# TIASch.net
KiCad netlist of a schematic drawn in Altium Designer
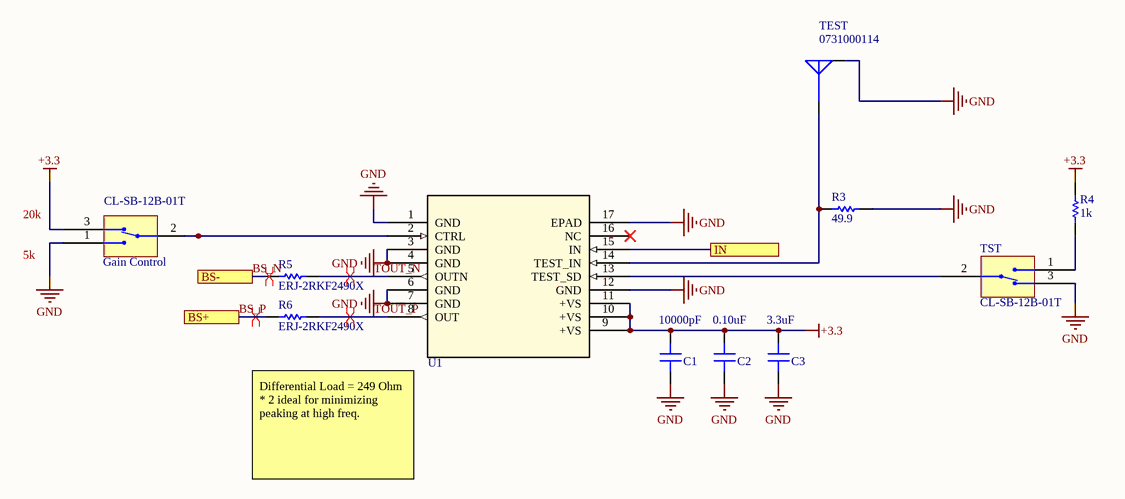
[diagram p0: TIASch.SchDoc]

(export (version "E")
  (design (tool "Eeschema 10.0.6"))
  (components
    (comp (ref "C1")
      (value "10000pF")
      (footprint "CAP 0402/1005")
      (description "CAP CER 10000PF 16V X7R 0402")
      (fields (field (name "PART NUMBER") "C0402C103J4RACTU") (field (name "MANUFACTURER") "Kemet"))
      (libsource (lib "Celestial Library Database") (part "Capacitor"))
    )
    (comp (ref "C2")
      (value "0.10uF")
      (footprint "CAP 0402/1005")
      (description "CAP CER 0.1UF 16V X7R 0402")
      (fields
        (field (name "PART NUMBER") "GRM155R71C104JA88D")
        (field (name "MANUFACTURER") "Murata Electronics North America")
      )
      (libsource (lib "Celestial Library Database") (part "Capacitor"))
    )
    (comp (ref "C3")
      (value "3.3uF")
      (footprint "CAP 0805/2012")
      (description "CAP CER 3.3UF 16V X7R 0805")
      (fields
        (field (name "PART NUMBER") "C2012X7R1C335K125AB")
        (field (name "MANUFACTURER") "TDK Corporation")
      )
      (libsource (lib "Celestial Library Database") (part "Capacitor"))
    )
    (comp (ref "Gain Control")
      (value "CL-SB-12B-01T")
      (footprint "SW_CL-SB-12B-01")
      (description "SWITCH SLIDE SPDT 200MA 12V")
      (fields (field (name "MANUFACTURER") "Nidec Copal Electronics"))
      (libsource (lib "") (part "CL-SB-12B-01T_1"))
    )
    (comp (ref "R3")
      (value "49.9")
      (footprint "RESC1005X40X25NL05T05")
      (fields (field (name "MANUFACTURER") "Panasonic") (field (name "PART NUMBER") "ERJ-2RKF49R9X"))
      (libsource (lib "Altium Content Vault") (part "RES"))
    )
    (comp (ref "R4")
      (value "1k")
      (footprint "RESC1005X40X25NL05T05")
      (description "Chip Resistor, 1 KOhm, +/- 1%, 100 mW, -55 to 155 degC, 0402 (1005 Metric), RoHS, Tape and Reel")
      (fields (field (name "PARTNUMBER") "ERJ-2RKF1001X") (field (name "MANUFACTURER") "Basic Passives"))
      (libsource (lib "Altium Content Vault") (part "RES-2"))
    )
    (comp (ref "R5")
      (value "ERJ-2RKF2490X")
      (footprint "RESC1005X40X25NL05T05")
      (fields (field (name "MANUFACTURER") "Panasonic"))
      (libsource (lib "Altium Content Vault") (part "RES"))
    )
    (comp (ref "R6")
      (value "ERJ-2RKF2490X")
      (footprint "RESC1005X40X25NL05T05")
      (fields (field (name "MANUFACTURER") "Panasonic"))
      (libsource (lib "Altium Content Vault") (part "RES"))
    )
    (comp (ref "TEST")
      (value "0731000114")
      (footprint "MOLEX SD-73100-0114")
      (description "CONN SMA RCPT R/A 50 OHM PCB")
      (fields (field (name "MANUFACTURER") "Molex"))
      (libsource (lib "Celestial Library Database") (part "RF Connector - SMA"))
    )
    (comp (ref "TST")
      (value "CL-SB-12B-01T")
      (footprint "SW_CL-SB-12B-01")
      (description "SWITCH SLIDE SPDT 200MA 12V")
      (fields (field (name "MANUFACTURER") "Nidec Copal Electronics"))
      (libsource (lib "Celestial Library Database") (part "CL-SB-12B-01T"))
    )
    (comp (ref "U1")
      (value "OPA857")
      (footprint "TI VQFN-16 (3x3)")
      (description "IC OPAMP GP 1 CIRCUIT 16VQFN")
      (fields
        (field (name "MANUFACTURER_PART_NUMBER") "OPA857IRGTT")
        (field (name "MANUFACTURER") "Texas Instruments")
        (field (name "COPYRIGHT") "Copyright (C) 2018 Accelerated Designs. All rights reserved")
      )
      (libsource (lib "Celestial Library Database") (part "OPA857IRGTT"))
    )
  )
  (nets
    (net (code "1") (name "+3.3") (class "Default")
      (node (ref "C1") (pin "2") (pinfunction "2_2") (pintype "passive"))
      (node (ref "C2") (pin "2") (pinfunction "2_2") (pintype "passive"))
      (node (ref "C3") (pin "2") (pinfunction "2_2") (pintype "passive"))
      (node (ref "Gain Control") (pin "3") (pinfunction "GND_3") (pintype "passive"))
      (node (ref "R4") (pin "1") (pinfunction "1_1") (pintype "passive"))
      (node (ref "U1") (pin "10") (pinfunction "+VS_10") (pintype "power_in"))
      (node (ref "U1") (pin "11") (pinfunction "+VS_11") (pintype "power_in"))
      (node (ref "U1") (pin "9") (pinfunction "+VS_9") (pintype "power_in"))
    )
    (net (code "2") (name "/BS_N") (class "Default")
      (node (ref "R5") (pin "1") (pinfunction "1_1") (pintype "passive"))
    )
    (net (code "3") (name "/BS_P") (class "Default")
      (node (ref "R6") (pin "1") (pinfunction "1_1") (pintype "passive"))
    )
    (net (code "4") (name "/IN") (class "Default")
      (node (ref "U1") (pin "15") (pinfunction "IN_15") (pintype "input"))
    )
    (net (code "5") (name "/TOUT_N") (class "Default")
      (node (ref "R5") (pin "2") (pinfunction "2_2") (pintype "passive"))
      (node (ref "U1") (pin "5") (pinfunction "OUTN_5") (pintype "output"))
    )
    (net (code "6") (name "/TOUT_P") (class "Default")
      (node (ref "R6") (pin "2") (pinfunction "2_2") (pintype "passive"))
      (node (ref "U1") (pin "8") (pinfunction "OUT_8") (pintype "output"))
    )
    (net (code "7") (name "GND") (class "Default")
      (node (ref "C1") (pin "1") (pinfunction "1_1") (pintype "passive"))
      (node (ref "C2") (pin "1") (pinfunction "1_1") (pintype "passive"))
      (node (ref "C3") (pin "1") (pinfunction "1_1") (pintype "passive"))
      (node (ref "Gain Control") (pin "1") (pinfunction "GND_1") (pintype "passive"))
      (node (ref "R3") (pin "2") (pinfunction "2_2") (pintype "passive"))
      (node (ref "TEST") (pin "G") (pinfunction "G_G") (pintype "passive"))
      (node (ref "TST") (pin "3") (pinfunction "GND_3") (pintype "passive"))
      (node (ref "U1") (pin "1") (pinfunction "GND_1") (pintype "power_in"))
      (node (ref "U1") (pin "12") (pinfunction "GND_12") (pintype "power_in"))
      (node (ref "U1") (pin "17") (pinfunction "EPAD_17") (pintype "passive"))
      (node (ref "U1") (pin "3") (pinfunction "GND_3") (pintype "power_in"))
      (node (ref "U1") (pin "4") (pinfunction "GND_4") (pintype "power_in"))
      (node (ref "U1") (pin "6") (pinfunction "GND_6") (pintype "power_in"))
      (node (ref "U1") (pin "7") (pinfunction "GND_7") (pintype "power_in"))
    )
    (net (code "8") (name "Net-(R4-Pad2)") (class "Default")
      (node (ref "R4") (pin "2") (pinfunction "2_2") (pintype "passive"))
      (node (ref "TST") (pin "1") (pinfunction "GND_1") (pintype "passive"))
    )
    (net (code "9") (name "Net-(U1-CTRL)") (class "Default")
      (node (ref "Gain Control") (pin "2") (pinfunction "GND_2") (pintype "passive"))
      (node (ref "U1") (pin "2") (pinfunction "CTRL_2") (pintype "input"))
    )
    (net (code "10") (name "Net-(U1-TEST_IN)") (class "Default")
      (node (ref "R3") (pin "1") (pinfunction "1_1") (pintype "passive"))
      (node (ref "TEST") (pin "S") (pinfunction "S_S") (pintype "passive"))
      (node (ref "U1") (pin "14") (pinfunction "TEST_IN_14") (pintype "input"))
    )
    (net (code "11") (name "Net-(U1-TEST_SD)") (class "Default")
      (node (ref "TST") (pin "2") (pinfunction "GND_2") (pintype "passive"))
      (node (ref "U1") (pin "13") (pinfunction "TEST_SD_13") (pintype "input"))
    )
    (net (code "12") (name "unconnected-(U1-NC-Pad16)") (class "Default")
      (node (ref "U1") (pin "16") (pinfunction "NC_16") (pintype "passive+no_connect"))
    )
  )
)
